# Connectors.net
KiCad netlist of a schematic drawn in Altium Designer
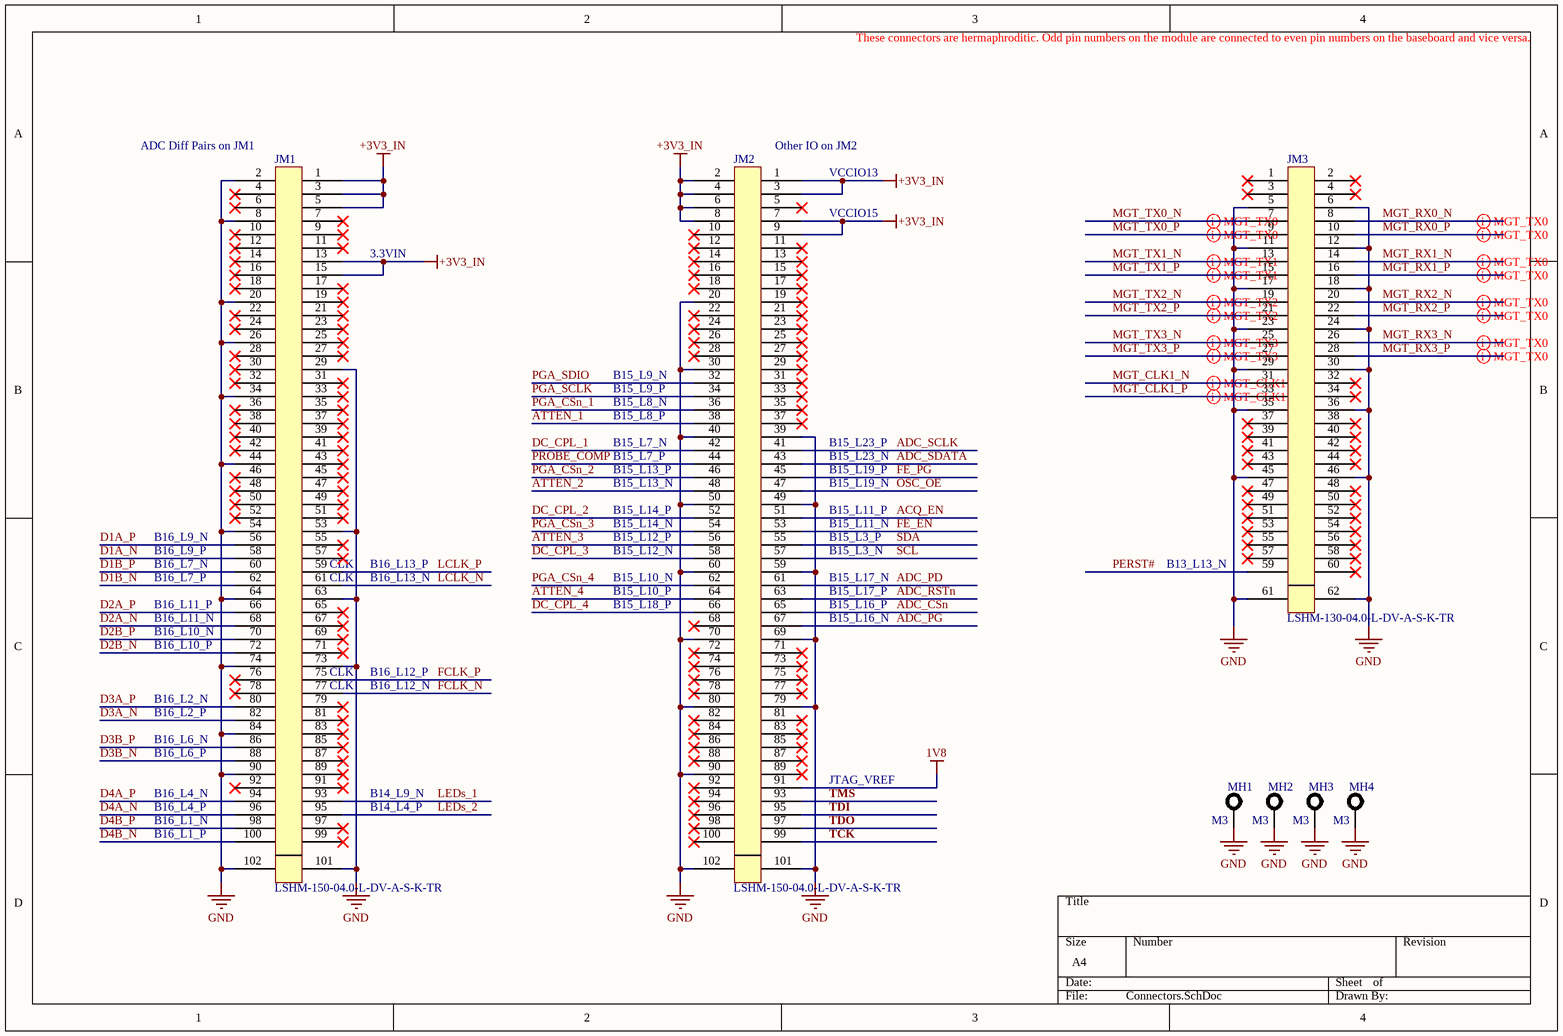
[diagram p0: Connectors.SchDoc]

(export (version "E")
  (design (tool "Eeschema 10.0.6"))
  (components
    (comp (ref "JM1")
      (value "LSHM-150-04.0-L-DV-A-S-K-TR")
      (footprint "SAM_LSHM-150-XX.X-XX-DV-A-S")
      (libsource (lib "DSO") (part "CONN LSHM-150-04.0-L-DV-A-S-K-TR"))
    )
    (comp (ref "JM2")
      (value "LSHM-150-04.0-L-DV-A-S-K-TR")
      (footprint "SAM_LSHM-150-XX.X-XX-DV-A-S")
      (libsource (lib "DSO") (part "CONN LSHM-150-04.0-L-DV-A-S-K-TR"))
    )
    (comp (ref "JM3")
      (value "LSHM-130-04.0-L-DV-A-S-K-TR")
      (footprint "SAM_LSHM-130-XX.X-XX-DV-A-S")
      (libsource (lib "DSO") (part "CONN LSHM-130-04.0-L-DV-A-S-K-TR"))
    )
    (comp (ref "MH1") (value "M3") (footprint "MH M3") (libsource (lib "DSO") (part "MH M3")))
    (comp (ref "MH2") (value "M3") (footprint "MH M3") (libsource (lib "DSO") (part "MH M3")))
    (comp (ref "MH3") (value "M3") (footprint "MH M3") (libsource (lib "DSO") (part "MH M3")))
    (comp (ref "MH4") (value "M3") (footprint "MH M3") (libsource (lib "DSO") (part "MH M3")))
  )
  (nets
    (net (code "1") (name "+3V3_IN") (class "Default")
      (node (ref "JM1") (pin "1") (pinfunction "1_1") (pintype "passive"))
      (node (ref "JM1") (pin "13") (pinfunction "13_13") (pintype "passive"))
      (node (ref "JM1") (pin "15") (pinfunction "15_15") (pintype "passive"))
      (node (ref "JM1") (pin "3") (pinfunction "3_3") (pintype "passive"))
      (node (ref "JM1") (pin "5") (pinfunction "5_5") (pintype "passive"))
      (node (ref "JM2") (pin "1") (pinfunction "1_1") (pintype "passive"))
      (node (ref "JM2") (pin "2") (pinfunction "2_2") (pintype "passive"))
      (node (ref "JM2") (pin "3") (pinfunction "3_3") (pintype "passive"))
      (node (ref "JM2") (pin "4") (pinfunction "4_4") (pintype "passive"))
      (node (ref "JM2") (pin "6") (pinfunction "6_6") (pintype "passive"))
      (node (ref "JM2") (pin "7") (pinfunction "7_7") (pintype "passive"))
      (node (ref "JM2") (pin "8") (pinfunction "8_8") (pintype "passive"))
      (node (ref "JM2") (pin "9") (pinfunction "9_9") (pintype "passive"))
    )
    (net (code "2") (name "/ACQ_EN") (class "Default")
      (node (ref "JM2") (pin "51") (pinfunction "51_51") (pintype "passive"))
    )
    (net (code "3") (name "/ADC_CSn") (class "Default")
      (node (ref "JM2") (pin "65") (pinfunction "65_65") (pintype "passive"))
    )
    (net (code "4") (name "/ADC_PD") (class "Default")
      (node (ref "JM2") (pin "61") (pinfunction "61_61") (pintype "passive"))
    )
    (net (code "5") (name "/ADC_PG") (class "Default")
      (node (ref "JM2") (pin "67") (pinfunction "67_67") (pintype "passive"))
    )
    (net (code "6") (name "/ADC_RSTn") (class "Default")
      (node (ref "JM2") (pin "63") (pinfunction "63_63") (pintype "passive"))
    )
    (net (code "7") (name "/ADC_SCLK") (class "Default")
      (node (ref "JM2") (pin "41") (pinfunction "41_41") (pintype "passive"))
    )
    (net (code "8") (name "/ADC_SDATA") (class "Default")
      (node (ref "JM2") (pin "43") (pinfunction "43_43") (pintype "passive"))
    )
    (net (code "9") (name "/ATTEN_1") (class "Default")
      (node (ref "JM2") (pin "38") (pinfunction "38_38") (pintype "passive"))
    )
    (net (code "10") (name "/ATTEN_2") (class "Default")
      (node (ref "JM2") (pin "48") (pinfunction "48_48") (pintype "passive"))
    )
    (net (code "11") (name "/ATTEN_3") (class "Default")
      (node (ref "JM2") (pin "56") (pinfunction "56_56") (pintype "passive"))
    )
    (net (code "12") (name "/ATTEN_4") (class "Default")
      (node (ref "JM2") (pin "64") (pinfunction "64_64") (pintype "passive"))
    )
    (net (code "13") (name "/D1A_N") (class "Default")
      (node (ref "JM1") (pin "58") (pinfunction "58_58") (pintype "passive"))
    )
    (net (code "14") (name "/D1A_P") (class "Default")
      (node (ref "JM1") (pin "56") (pinfunction "56_56") (pintype "passive"))
    )
    (net (code "15") (name "/D1B_N") (class "Default")
      (node (ref "JM1") (pin "62") (pinfunction "62_62") (pintype "passive"))
    )
    (net (code "16") (name "/D1B_P") (class "Default")
      (node (ref "JM1") (pin "60") (pinfunction "60_60") (pintype "passive"))
    )
    (net (code "17") (name "/D2A_N") (class "Default")
      (node (ref "JM1") (pin "68") (pinfunction "68_68") (pintype "passive"))
    )
    (net (code "18") (name "/D2A_P") (class "Default")
      (node (ref "JM1") (pin "66") (pinfunction "66_66") (pintype "passive"))
    )
    (net (code "19") (name "/D2B_N") (class "Default")
      (node (ref "JM1") (pin "72") (pinfunction "72_72") (pintype "passive"))
    )
    (net (code "20") (name "/D2B_P") (class "Default")
      (node (ref "JM1") (pin "70") (pinfunction "70_70") (pintype "passive"))
    )
    (net (code "21") (name "/D3A_N") (class "Default")
      (node (ref "JM1") (pin "82") (pinfunction "82_82") (pintype "passive"))
    )
    (net (code "22") (name "/D3A_P") (class "Default")
      (node (ref "JM1") (pin "80") (pinfunction "80_80") (pintype "passive"))
    )
    (net (code "23") (name "/D3B_N") (class "Default")
      (node (ref "JM1") (pin "88") (pinfunction "88_88") (pintype "passive"))
    )
    (net (code "24") (name "/D3B_P") (class "Default")
      (node (ref "JM1") (pin "86") (pinfunction "86_86") (pintype "passive"))
    )
    (net (code "25") (name "/D4A_N") (class "Default")
      (node (ref "JM1") (pin "96") (pinfunction "96_96") (pintype "passive"))
    )
    (net (code "26") (name "/D4A_P") (class "Default")
      (node (ref "JM1") (pin "94") (pinfunction "94_94") (pintype "passive"))
    )
    (net (code "27") (name "/D4B_N") (class "Default")
      (node (ref "JM1") (pin "100") (pinfunction "100_100") (pintype "passive"))
    )
    (net (code "28") (name "/D4B_P") (class "Default")
      (node (ref "JM1") (pin "98") (pinfunction "98_98") (pintype "passive"))
    )
    (net (code "29") (name "/DC_CPL_1") (class "Default")
      (node (ref "JM2") (pin "42") (pinfunction "42_42") (pintype "passive"))
    )
    (net (code "30") (name "/DC_CPL_2") (class "Default")
      (node (ref "JM2") (pin "52") (pinfunction "52_52") (pintype "passive"))
    )
    (net (code "31") (name "/DC_CPL_3") (class "Default")
      (node (ref "JM2") (pin "58") (pinfunction "58_58") (pintype "passive"))
    )
    (net (code "32") (name "/DC_CPL_4") (class "Default")
      (node (ref "JM2") (pin "66") (pinfunction "66_66") (pintype "passive"))
    )
    (net (code "33") (name "/FCLK_N") (class "Default")
      (node (ref "JM1") (pin "77") (pinfunction "77_77") (pintype "passive"))
    )
    (net (code "34") (name "/FCLK_P") (class "Default")
      (node (ref "JM1") (pin "75") (pinfunction "75_75") (pintype "passive"))
    )
    (net (code "35") (name "/FE_EN") (class "Default")
      (node (ref "JM2") (pin "53") (pinfunction "53_53") (pintype "passive"))
    )
    (net (code "36") (name "/FE_PG") (class "Default")
      (node (ref "JM2") (pin "45") (pinfunction "45_45") (pintype "passive"))
    )
    (net (code "37") (name "/LCLK_N") (class "Default")
      (node (ref "JM1") (pin "61") (pinfunction "61_61") (pintype "passive"))
    )
    (net (code "38") (name "/LCLK_P") (class "Default")
      (node (ref "JM1") (pin "59") (pinfunction "59_59") (pintype "passive"))
    )
    (net (code "39") (name "/LEDs_1") (class "Default")
      (node (ref "JM1") (pin "93") (pinfunction "93_93") (pintype "passive"))
    )
    (net (code "40") (name "/LEDs_2") (class "Default")
      (node (ref "JM1") (pin "95") (pinfunction "95_95") (pintype "passive"))
    )
    (net (code "41") (name "/MGT_CLK1_N") (class "Default")
      (node (ref "JM3") (pin "31") (pinfunction "31_31") (pintype "passive"))
    )
    (net (code "42") (name "/MGT_CLK1_P") (class "Default")
      (node (ref "JM3") (pin "33") (pinfunction "33_33") (pintype "passive"))
    )
    (net (code "43") (name "/MGT_RX0_N") (class "Default")
      (node (ref "JM3") (pin "8") (pinfunction "8_8") (pintype "passive"))
    )
    (net (code "44") (name "/MGT_RX0_P") (class "Default")
      (node (ref "JM3") (pin "10") (pinfunction "10_10") (pintype "passive"))
    )
    (net (code "45") (name "/MGT_RX1_N") (class "Default")
      (node (ref "JM3") (pin "14") (pinfunction "14_14") (pintype "passive"))
    )
    (net (code "46") (name "/MGT_RX1_P") (class "Default")
      (node (ref "JM3") (pin "16") (pinfunction "16_16") (pintype "passive"))
    )
    (net (code "47") (name "/MGT_RX2_N") (class "Default")
      (node (ref "JM3") (pin "20") (pinfunction "20_20") (pintype "passive"))
    )
    (net (code "48") (name "/MGT_RX2_P") (class "Default")
      (node (ref "JM3") (pin "22") (pinfunction "22_22") (pintype "passive"))
    )
    (net (code "49") (name "/MGT_RX3_N") (class "Default")
      (node (ref "JM3") (pin "26") (pinfunction "26_26") (pintype "passive"))
    )
    (net (code "50") (name "/MGT_RX3_P") (class "Default")
      (node (ref "JM3") (pin "28") (pinfunction "28_28") (pintype "passive"))
    )
    (net (code "51") (name "/MGT_TX0_N") (class "Default")
      (node (ref "JM3") (pin "7") (pinfunction "7_7") (pintype "passive"))
    )
    (net (code "52") (name "/MGT_TX0_P") (class "Default")
      (node (ref "JM3") (pin "9") (pinfunction "9_9") (pintype "passive"))
    )
    (net (code "53") (name "/MGT_TX1_N") (class "Default")
      (node (ref "JM3") (pin "13") (pinfunction "13_13") (pintype "passive"))
    )
    (net (code "54") (name "/MGT_TX1_P") (class "Default")
      (node (ref "JM3") (pin "15") (pinfunction "15_15") (pintype "passive"))
    )
    (net (code "55") (name "/MGT_TX2_N") (class "Default")
      (node (ref "JM3") (pin "19") (pinfunction "19_19") (pintype "passive"))
    )
    (net (code "56") (name "/MGT_TX2_P") (class "Default")
      (node (ref "JM3") (pin "21") (pinfunction "21_21") (pintype "passive"))
    )
    (net (code "57") (name "/MGT_TX3_N") (class "Default")
      (node (ref "JM3") (pin "25") (pinfunction "25_25") (pintype "passive"))
    )
    (net (code "58") (name "/MGT_TX3_P") (class "Default")
      (node (ref "JM3") (pin "27") (pinfunction "27_27") (pintype "passive"))
    )
    (net (code "59") (name "/OSC_OE") (class "Default")
      (node (ref "JM2") (pin "47") (pinfunction "47_47") (pintype "passive"))
    )
    (net (code "60") (name "/PERST#") (class "Default")
      (node (ref "JM3") (pin "59") (pinfunction "59_59") (pintype "passive"))
    )
    (net (code "61") (name "/PGA_CSn_1") (class "Default")
      (node (ref "JM2") (pin "36") (pinfunction "36_36") (pintype "passive"))
    )
    (net (code "62") (name "/PGA_CSn_2") (class "Default")
      (node (ref "JM2") (pin "46") (pinfunction "46_46") (pintype "passive"))
    )
    (net (code "63") (name "/PGA_CSn_3") (class "Default")
      (node (ref "JM2") (pin "54") (pinfunction "54_54") (pintype "passive"))
    )
    (net (code "64") (name "/PGA_CSn_4") (class "Default")
      (node (ref "JM2") (pin "62") (pinfunction "62_62") (pintype "passive"))
    )
    (net (code "65") (name "/PGA_SCLK") (class "Default")
      (node (ref "JM2") (pin "34") (pinfunction "34_34") (pintype "passive"))
    )
    (net (code "66") (name "/PGA_SDIO") (class "Default")
      (node (ref "JM2") (pin "32") (pinfunction "32_32") (pintype "passive"))
    )
    (net (code "67") (name "/PROBE_COMP") (class "Default")
      (node (ref "JM2") (pin "44") (pinfunction "44_44") (pintype "passive"))
    )
    (net (code "68") (name "/SCL") (class "Default")
      (node (ref "JM2") (pin "57") (pinfunction "57_57") (pintype "passive"))
    )
    (net (code "69") (name "/SDA") (class "Default")
      (node (ref "JM2") (pin "55") (pinfunction "55_55") (pintype "passive"))
    )
    (net (code "70") (name "/TCK") (class "Default")
      (node (ref "JM2") (pin "99") (pinfunction "99_99") (pintype "passive"))
    )
    (net (code "71") (name "/TDI") (class "Default")
      (node (ref "JM2") (pin "95") (pinfunction "95_95") (pintype "passive"))
    )
    (net (code "72") (name "/TDO") (class "Default")
      (node (ref "JM2") (pin "97") (pinfunction "97_97") (pintype "passive"))
    )
    (net (code "73") (name "/TMS") (class "Default")
      (node (ref "JM2") (pin "93") (pinfunction "93_93") (pintype "passive"))
    )
    (net (code "74") (name "1V8") (class "Default")
      (node (ref "JM2") (pin "91") (pinfunction "91_91") (pintype "passive"))
    )
    (net (code "75") (name "GND") (class "Default")
      (node (ref "JM1") (pin "101") (pinfunction "101_101") (pintype "passive"))
      (node (ref "JM1") (pin "102") (pinfunction "102_102") (pintype "passive"))
      (node (ref "JM1") (pin "2") (pinfunction "2_2") (pintype "passive"))
      (node (ref "JM1") (pin "20") (pinfunction "20_20") (pintype "passive"))
      (node (ref "JM1") (pin "26") (pinfunction "26_26") (pintype "passive"))
      (node (ref "JM1") (pin "29") (pinfunction "29_29") (pintype "passive"))
      (node (ref "JM1") (pin "34") (pinfunction "34_34") (pintype "passive"))
      (node (ref "JM1") (pin "44") (pinfunction "44_44") (pintype "passive"))
      (node (ref "JM1") (pin "53") (pinfunction "53_53") (pintype "passive"))
      (node (ref "JM1") (pin "54") (pinfunction "54_54") (pintype "passive"))
      (node (ref "JM1") (pin "63") (pinfunction "63_63") (pintype "passive"))
      (node (ref "JM1") (pin "64") (pinfunction "64_64") (pintype "passive"))
      (node (ref "JM1") (pin "73") (pinfunction "73_73") (pintype "passive"))
      (node (ref "JM1") (pin "74") (pinfunction "74_74") (pintype "passive"))
      (node (ref "JM1") (pin "8") (pinfunction "8_8") (pintype "passive"))
      (node (ref "JM1") (pin "84") (pinfunction "84_84") (pintype "passive"))
      (node (ref "JM1") (pin "90") (pinfunction "90_90") (pintype "passive"))
      (node (ref "JM2") (pin "101") (pinfunction "101_101") (pintype "passive"))
      (node (ref "JM2") (pin "102") (pinfunction "102_102") (pintype "passive"))
      (node (ref "JM2") (pin "20") (pinfunction "20_20") (pintype "passive"))
      (node (ref "JM2") (pin "30") (pinfunction "30_30") (pintype "passive"))
      (node (ref "JM2") (pin "39") (pinfunction "39_39") (pintype "passive"))
      (node (ref "JM2") (pin "40") (pinfunction "40_40") (pintype "passive"))
      (node (ref "JM2") (pin "49") (pinfunction "49_49") (pintype "passive"))
      (node (ref "JM2") (pin "50") (pinfunction "50_50") (pintype "passive"))
      (node (ref "JM2") (pin "59") (pinfunction "59_59") (pintype "passive"))
      (node (ref "JM2") (pin "60") (pinfunction "60_60") (pintype "passive"))
      (node (ref "JM2") (pin "69") (pinfunction "69_69") (pintype "passive"))
      (node (ref "JM2") (pin "70") (pinfunction "70_70") (pintype "passive"))
      (node (ref "JM2") (pin "79") (pinfunction "79_79") (pintype "passive"))
      (node (ref "JM2") (pin "80") (pinfunction "80_80") (pintype "passive"))
      (node (ref "JM2") (pin "90") (pinfunction "90_90") (pintype "passive"))
      (node (ref "JM3") (pin "11") (pinfunction "11_11") (pintype "passive"))
      (node (ref "JM3") (pin "12") (pinfunction "12_12") (pintype "passive"))
      (node (ref "JM3") (pin "17") (pinfunction "17_17") (pintype "passive"))
      (node (ref "JM3") (pin "18") (pinfunction "18_18") (pintype "passive"))
      (node (ref "JM3") (pin "23") (pinfunction "23_23") (pintype "passive"))
      (node (ref "JM3") (pin "24") (pinfunction "24_24") (pintype "passive"))
      (node (ref "JM3") (pin "29") (pinfunction "29_29") (pintype "passive"))
      (node (ref "JM3") (pin "30") (pinfunction "30_30") (pintype "passive"))
      (node (ref "JM3") (pin "35") (pinfunction "35_35") (pintype "passive"))
      (node (ref "JM3") (pin "36") (pinfunction "36_36") (pintype "passive"))
      (node (ref "JM3") (pin "45") (pinfunction "45_45") (pintype "passive"))
      (node (ref "JM3") (pin "46") (pinfunction "46_46") (pintype "passive"))
      (node (ref "JM3") (pin "5") (pinfunction "5_5") (pintype "passive"))
      (node (ref "JM3") (pin "6") (pinfunction "6_6") (pintype "passive"))
      (node (ref "JM3") (pin "61") (pinfunction "61_61") (pintype "passive"))
      (node (ref "JM3") (pin "62") (pinfunction "62_62") (pintype "passive"))
      (node (ref "MH1") (pin "1") (pinfunction "1_1") (pintype "passive"))
      (node (ref "MH2") (pin "1") (pinfunction "1_1") (pintype "passive"))
      (node (ref "MH3") (pin "1") (pinfunction "1_1") (pintype "passive"))
      (node (ref "MH4") (pin "1") (pinfunction "1_1") (pintype "passive"))
    )
    (net (code "76") (name "unconnected-(JM1-Pad4)") (class "Default")
      (node (ref "JM1") (pin "4") (pinfunction "4_4") (pintype "passive+no_connect"))
    )
    (net (code "77") (name "unconnected-(JM1-Pad6)") (class "Default")
      (node (ref "JM1") (pin "6") (pinfunction "6_6") (pintype "passive+no_connect"))
    )
    (net (code "78") (name "unconnected-(JM1-Pad7)") (class "Default")
      (node (ref "JM1") (pin "7") (pinfunction "7_7") (pintype "passive+no_connect"))
    )
    (net (code "79") (name "unconnected-(JM1-Pad9)") (class "Default")
      (node (ref "JM1") (pin "9") (pinfunction "9_9") (pintype "passive+no_connect"))
    )
    (net (code "80") (name "unconnected-(JM1-Pad10)") (class "Default")
      (node (ref "JM1") (pin "10") (pinfunction "10_10") (pintype "passive+no_connect"))
    )
    (net (code "81") (name "unconnected-(JM1-Pad11)") (class "Default")
      (node (ref "JM1") (pin "11") (pinfunction "11_11") (pintype "passive+no_connect"))
    )
    (net (code "82") (name "unconnected-(JM1-Pad12)") (class "Default")
      (node (ref "JM1") (pin "12") (pinfunction "12_12") (pintype "passive+no_connect"))
    )
    (net (code "83") (name "unconnected-(JM1-Pad14)") (class "Default")
      (node (ref "JM1") (pin "14") (pinfunction "14_14") (pintype "passive+no_connect"))
    )
    (net (code "84") (name "unconnected-(JM1-Pad16)") (class "Default")
      (node (ref "JM1") (pin "16") (pinfunction "16_16") (pintype "passive+no_connect"))
    )
    (net (code "85") (name "unconnected-(JM1-Pad17)") (class "Default")
      (node (ref "JM1") (pin "17") (pinfunction "17_17") (pintype "passive+no_connect"))
    )
    (net (code "86") (name "unconnected-(JM1-Pad18)") (class "Default")
      (node (ref "JM1") (pin "18") (pinfunction "18_18") (pintype "passive+no_connect"))
    )
    (net (code "87") (name "unconnected-(JM1-Pad19)") (class "Default")
      (node (ref "JM1") (pin "19") (pinfunction "19_19") (pintype "passive+no_connect"))
    )
    (net (code "88") (name "unconnected-(JM1-Pad21)") (class "Default")
      (node (ref "JM1") (pin "21") (pinfunction "21_21") (pintype "passive+no_connect"))
    )
    (net (code "89") (name "unconnected-(JM1-Pad22)") (class "Default")
      (node (ref "JM1") (pin "22") (pinfunction "22_22") (pintype "passive+no_connect"))
    )
    (net (code "90") (name "unconnected-(JM1-Pad23)") (class "Default")
      (node (ref "JM1") (pin "23") (pinfunction "23_23") (pintype "passive+no_connect"))
    )
    (net (code "91") (name "unconnected-(JM1-Pad24)") (class "Default")
      (node (ref "JM1") (pin "24") (pinfunction "24_24") (pintype "passive+no_connect"))
    )
    (net (code "92") (name "unconnected-(JM1-Pad25)") (class "Default")
      (node (ref "JM1") (pin "25") (pinfunction "25_25") (pintype "passive+no_connect"))
    )
    (net (code "93") (name "unconnected-(JM1-Pad27)") (class "Default")
      (node (ref "JM1") (pin "27") (pinfunction "27_27") (pintype "passive+no_connect"))
    )
    (net (code "94") (name "unconnected-(JM1-Pad28)") (class "Default")
      (node (ref "JM1") (pin "28") (pinfunction "28_28") (pintype "passive+no_connect"))
    )
    (net (code "95") (name "unconnected-(JM1-Pad30)") (class "Default")
      (node (ref "JM1") (pin "30") (pinfunction "30_30") (pintype "passive+no_connect"))
    )
    (net (code "96") (name "unconnected-(JM1-Pad31)") (class "Default")
      (node (ref "JM1") (pin "31") (pinfunction "31_31") (pintype "passive+no_connect"))
    )
    (net (code "97") (name "unconnected-(JM1-Pad32)") (class "Default")
      (node (ref "JM1") (pin "32") (pinfunction "32_32") (pintype "passive+no_connect"))
    )
    (net (code "98") (name "unconnected-(JM1-Pad33)") (class "Default")
      (node (ref "JM1") (pin "33") (pinfunction "33_33") (pintype "passive+no_connect"))
    )
    (net (code "99") (name "unconnected-(JM1-Pad35)") (class "Default")
      (node (ref "JM1") (pin "35") (pinfunction "35_35") (pintype "passive+no_connect"))
    )
    (net (code "100") (name "unconnected-(JM1-Pad36)") (class "Default")
      (node (ref "JM1") (pin "36") (pinfunction "36_36") (pintype "passive+no_connect"))
    )
    (net (code "101") (name "unconnected-(JM1-Pad37)") (class "Default")
      (node (ref "JM1") (pin "37") (pinfunction "37_37") (pintype "passive+no_connect"))
    )
    (net (code "102") (name "unconnected-(JM1-Pad38)") (class "Default")
      (node (ref "JM1") (pin "38") (pinfunction "38_38") (pintype "passive+no_connect"))
    )
    (net (code "103") (name "unconnected-(JM1-Pad39)") (class "Default")
      (node (ref "JM1") (pin "39") (pinfunction "39_39") (pintype "passive+no_connect"))
    )
    (net (code "104") (name "unconnected-(JM1-Pad40)") (class "Default")
      (node (ref "JM1") (pin "40") (pinfunction "40_40") (pintype "passive+no_connect"))
    )
    (net (code "105") (name "unconnected-(JM1-Pad41)") (class "Default")
      (node (ref "JM1") (pin "41") (pinfunction "41_41") (pintype "passive+no_connect"))
    )
    (net (code "106") (name "unconnected-(JM1-Pad42)") (class "Default")
      (node (ref "JM1") (pin "42") (pinfunction "42_42") (pintype "passive+no_connect"))
    )
    (net (code "107") (name "unconnected-(JM1-Pad43)") (class "Default")
      (node (ref "JM1") (pin "43") (pinfunction "43_43") (pintype "passive+no_connect"))
    )
    (net (code "108") (name "unconnected-(JM1-Pad45)") (class "Default")
      (node (ref "JM1") (pin "45") (pinfunction "45_45") (pintype "passive+no_connect"))
    )
    (net (code "109") (name "unconnected-(JM1-Pad46)") (class "Default")
      (node (ref "JM1") (pin "46") (pinfunction "46_46") (pintype "passive+no_connect"))
    )
    (net (code "110") (name "unconnected-(JM1-Pad47)") (class "Default")
      (node (ref "JM1") (pin "47") (pinfunction "47_47") (pintype "passive+no_connect"))
    )
    (net (code "111") (name "unconnected-(JM1-Pad48)") (class "Default")
      (node (ref "JM1") (pin "48") (pinfunction "48_48") (pintype "passive+no_connect"))
    )
    (net (code "112") (name "unconnected-(JM1-Pad49)") (class "Default")
      (node (ref "JM1") (pin "49") (pinfunction "49_49") (pintype "passive+no_connect"))
    )
    (net (code "113") (name "unconnected-(JM1-Pad50)") (class "Default")
      (node (ref "JM1") (pin "50") (pinfunction "50_50") (pintype "passive+no_connect"))
    )
    (net (code "114") (name "unconnected-(JM1-Pad51)") (class "Default")
      (node (ref "JM1") (pin "51") (pinfunction "51_51") (pintype "passive+no_connect"))
    )
    (net (code "115") (name "unconnected-(JM1-Pad52)") (class "Default")
      (node (ref "JM1") (pin "52") (pinfunction "52_52") (pintype "passive+no_connect"))
    )
    (net (code "116") (name "unconnected-(JM1-Pad55)") (class "Default")
      (node (ref "JM1") (pin "55") (pinfunction "55_55") (pintype "passive+no_connect"))
    )
    (net (code "117") (name "unconnected-(JM1-Pad57)") (class "Default")
      (node (ref "JM1") (pin "57") (pinfunction "57_57") (pintype "passive+no_connect"))
    )
    (net (code "118") (name "unconnected-(JM1-Pad65)") (class "Default")
      (node (ref "JM1") (pin "65") (pinfunction "65_65") (pintype "passive+no_connect"))
    )
    (net (code "119") (name "unconnected-(JM1-Pad67)") (class "Default")
      (node (ref "JM1") (pin "67") (pinfunction "67_67") (pintype "passive+no_connect"))
    )
    (net (code "120") (name "unconnected-(JM1-Pad69)") (class "Default")
      (node (ref "JM1") (pin "69") (pinfunction "69_69") (pintype "passive+no_connect"))
    )
    (net (code "121") (name "unconnected-(JM1-Pad71)") (class "Default")
      (node (ref "JM1") (pin "71") (pinfunction "71_71") (pintype "passive+no_connect"))
    )
    (net (code "122") (name "unconnected-(JM1-Pad76)") (class "Default")
      (node (ref "JM1") (pin "76") (pinfunction "76_76") (pintype "passive+no_connect"))
    )
    (net (code "123") (name "unconnected-(JM1-Pad78)") (class "Default")
      (node (ref "JM1") (pin "78") (pinfunction "78_78") (pintype "passive+no_connect"))
    )
    (net (code "124") (name "unconnected-(JM1-Pad79)") (class "Default")
      (node (ref "JM1") (pin "79") (pinfunction "79_79") (pintype "passive+no_connect"))
    )
    (net (code "125") (name "unconnected-(JM1-Pad81)") (class "Default")
      (node (ref "JM1") (pin "81") (pinfunction "81_81") (pintype "passive+no_connect"))
    )
    (net (code "126") (name "unconnected-(JM1-Pad83)") (class "Default")
      (node (ref "JM1") (pin "83") (pinfunction "83_83") (pintype "passive+no_connect"))
    )
    (net (code "127") (name "unconnected-(JM1-Pad85)") (class "Default")
      (node (ref "JM1") (pin "85") (pinfunction "85_85") (pintype "passive+no_connect"))
    )
    (net (code "128") (name "unconnected-(JM1-Pad87)") (class "Default")
      (node (ref "JM1") (pin "87") (pinfunction "87_87") (pintype "passive+no_connect"))
    )
    (net (code "129") (name "unconnected-(JM1-Pad89)") (class "Default")
      (node (ref "JM1") (pin "89") (pinfunction "89_89") (pintype "passive+no_connect"))
    )
    (net (code "130") (name "unconnected-(JM1-Pad91)") (class "Default")
      (node (ref "JM1") (pin "91") (pinfunction "91_91") (pintype "passive+no_connect"))
    )
    (net (code "131") (name "unconnected-(JM1-Pad92)") (class "Default")
      (node (ref "JM1") (pin "92") (pinfunction "92_92") (pintype "passive+no_connect"))
    )
    (net (code "132") (name "unconnected-(JM1-Pad97)") (class "Default")
      (node (ref "JM1") (pin "97") (pinfunction "97_97") (pintype "passive+no_connect"))
    )
    (net (code "133") (name "unconnected-(JM1-Pad99)") (class "Default")
      (node (ref "JM1") (pin "99") (pinfunction "99_99") (pintype "passive+no_connect"))
    )
    (net (code "134") (name "unconnected-(JM2-Pad5)") (class "Default")
      (node (ref "JM2") (pin "5") (pinfunction "5_5") (pintype "passive+no_connect"))
    )
    (net (code "135") (name "unconnected-(JM2-Pad10)") (class "Default")
      (node (ref "JM2") (pin "10") (pinfunction "10_10") (pintype "passive+no_connect"))
    )
    (net (code "136") (name "unconnected-(JM2-Pad11)") (class "Default")
      (node (ref "JM2") (pin "11") (pinfunction "11_11") (pintype "passive+no_connect"))
    )
    (net (code "137") (name "unconnected-(JM2-Pad12)") (class "Default")
      (node (ref "JM2") (pin "12") (pinfunction "12_12") (pintype "passive+no_connect"))
    )
    (net (code "138") (name "unconnected-(JM2-Pad13)") (class "Default")
      (node (ref "JM2") (pin "13") (pinfunction "13_13") (pintype "passive+no_connect"))
    )
    (net (code "139") (name "unconnected-(JM2-Pad14)") (class "Default")
      (node (ref "JM2") (pin "14") (pinfunction "14_14") (pintype "passive+no_connect"))
    )
    (net (code "140") (name "unconnected-(JM2-Pad15)") (class "Default")
      (node (ref "JM2") (pin "15") (pinfunction "15_15") (pintype "passive+no_connect"))
    )
    (net (code "141") (name "unconnected-(JM2-Pad16)") (class "Default")
      (node (ref "JM2") (pin "16") (pinfunction "16_16") (pintype "passive+no_connect"))
    )
    (net (code "142") (name "unconnected-(JM2-Pad17)") (class "Default")
      (node (ref "JM2") (pin "17") (pinfunction "17_17") (pintype "passive+no_connect"))
    )
    (net (code "143") (name "unconnected-(JM2-Pad18)") (class "Default")
      (node (ref "JM2") (pin "18") (pinfunction "18_18") (pintype "passive+no_connect"))
    )
    (net (code "144") (name "unconnected-(JM2-Pad19)") (class "Default")
      (node (ref "JM2") (pin "19") (pinfunction "19_19") (pintype "passive+no_connect"))
    )
    (net (code "145") (name "unconnected-(JM2-Pad21)") (class "Default")
      (node (ref "JM2") (pin "21") (pinfunction "21_21") (pintype "passive+no_connect"))
    )
    (net (code "146") (name "unconnected-(JM2-Pad22)") (class "Default")
      (node (ref "JM2") (pin "22") (pinfunction "22_22") (pintype "passive+no_connect"))
    )
    (net (code "147") (name "unconnected-(JM2-Pad23)") (class "Default")
      (node (ref "JM2") (pin "23") (pinfunction "23_23") (pintype "passive+no_connect"))
    )
    (net (code "148") (name "unconnected-(JM2-Pad24)") (class "Default")
      (node (ref "JM2") (pin "24") (pinfunction "24_24") (pintype "passive+no_connect"))
    )
    (net (code "149") (name "unconnected-(JM2-Pad25)") (class "Default")
      (node (ref "JM2") (pin "25") (pinfunction "25_25") (pintype "passive+no_connect"))
    )
    (net (code "150") (name "unconnected-(JM2-Pad26)") (class "Default")
      (node (ref "JM2") (pin "26") (pinfunction "26_26") (pintype "passive+no_connect"))
    )
    (net (code "151") (name "unconnected-(JM2-Pad27)") (class "Default")
      (node (ref "JM2") (pin "27") (pinfunction "27_27") (pintype "passive+no_connect"))
    )
    (net (code "152") (name "unconnected-(JM2-Pad28)") (class "Default")
      (node (ref "JM2") (pin "28") (pinfunction "28_28") (pintype "passive+no_connect"))
    )
    (net (code "153") (name "unconnected-(JM2-Pad29)") (class "Default")
      (node (ref "JM2") (pin "29") (pinfunction "29_29") (pintype "passive+no_connect"))
    )
    (net (code "154") (name "unconnected-(JM2-Pad31)") (class "Default")
      (node (ref "JM2") (pin "31") (pinfunction "31_31") (pintype "passive+no_connect"))
    )
    (net (code "155") (name "unconnected-(JM2-Pad33)") (class "Default")
      (node (ref "JM2") (pin "33") (pinfunction "33_33") (pintype "passive+no_connect"))
    )
    (net (code "156") (name "unconnected-(JM2-Pad35)") (class "Default")
      (node (ref "JM2") (pin "35") (pinfunction "35_35") (pintype "passive+no_connect"))
    )
    (net (code "157") (name "unconnected-(JM2-Pad37)") (class "Default")
      (node (ref "JM2") (pin "37") (pinfunction "37_37") (pintype "passive+no_connect"))
    )
    (net (code "158") (name "unconnected-(JM2-Pad68)") (class "Default")
      (node (ref "JM2") (pin "68") (pinfunction "68_68") (pintype "passive+no_connect"))
    )
    (net (code "159") (name "unconnected-(JM2-Pad71)") (class "Default")
      (node (ref "JM2") (pin "71") (pinfunction "71_71") (pintype "passive+no_connect"))
    )
    (net (code "160") (name "unconnected-(JM2-Pad72)") (class "Default")
      (node (ref "JM2") (pin "72") (pinfunction "72_72") (pintype "passive+no_connect"))
    )
    (net (code "161") (name "unconnected-(JM2-Pad73)") (class "Default")
      (node (ref "JM2") (pin "73") (pinfunction "73_73") (pintype "passive+no_connect"))
    )
    (net (code "162") (name "unconnected-(JM2-Pad74)") (class "Default")
      (node (ref "JM2") (pin "74") (pinfunction "74_74") (pintype "passive+no_connect"))
    )
    (net (code "163") (name "unconnected-(JM2-Pad75)") (class "Default")
      (node (ref "JM2") (pin "75") (pinfunction "75_75") (pintype "passive+no_connect"))
    )
    (net (code "164") (name "unconnected-(JM2-Pad76)") (class "Default")
      (node (ref "JM2") (pin "76") (pinfunction "76_76") (pintype "passive+no_connect"))
    )
    (net (code "165") (name "unconnected-(JM2-Pad77)") (class "Default")
      (node (ref "JM2") (pin "77") (pinfunction "77_77") (pintype "passive+no_connect"))
    )
    (net (code "166") (name "unconnected-(JM2-Pad78)") (class "Default")
      (node (ref "JM2") (pin "78") (pinfunction "78_78") (pintype "passive+no_connect"))
    )
    (net (code "167") (name "unconnected-(JM2-Pad81)") (class "Default")
      (node (ref "JM2") (pin "81") (pinfunction "81_81") (pintype "passive+no_connect"))
    )
    (net (code "168") (name "unconnected-(JM2-Pad82)") (class "Default")
      (node (ref "JM2") (pin "82") (pinfunction "82_82") (pintype "passive+no_connect"))
    )
    (net (code "169") (name "unconnected-(JM2-Pad83)") (class "Default")
      (node (ref "JM2") (pin "83") (pinfunction "83_83") (pintype "passive+no_connect"))
    )
    (net (code "170") (name "unconnected-(JM2-Pad84)") (class "Default")
      (node (ref "JM2") (pin "84") (pinfunction "84_84") (pintype "passive+no_connect"))
    )
    (net (code "171") (name "unconnected-(JM2-Pad85)") (class "Default")
      (node (ref "JM2") (pin "85") (pinfunction "85_85") (pintype "passive+no_connect"))
    )
    (net (code "172") (name "unconnected-(JM2-Pad86)") (class "Default")
      (node (ref "JM2") (pin "86") (pinfunction "86_86") (pintype "passive+no_connect"))
    )
    (net (code "173") (name "unconnected-(JM2-Pad87)") (class "Default")
      (node (ref "JM2") (pin "87") (pinfunction "87_87") (pintype "passive+no_connect"))
    )
    (net (code "174") (name "unconnected-(JM2-Pad88)") (class "Default")
      (node (ref "JM2") (pin "88") (pinfunction "88_88") (pintype "passive+no_connect"))
    )
    (net (code "175") (name "unconnected-(JM2-Pad89)") (class "Default")
      (node (ref "JM2") (pin "89") (pinfunction "89_89") (pintype "passive+no_connect"))
    )
    (net (code "176") (name "unconnected-(JM2-Pad92)") (class "Default")
      (node (ref "JM2") (pin "92") (pinfunction "92_92") (pintype "passive+no_connect"))
    )
    (net (code "177") (name "unconnected-(JM2-Pad94)") (class "Default")
      (node (ref "JM2") (pin "94") (pinfunction "94_94") (pintype "passive+no_connect"))
    )
    (net (code "178") (name "unconnected-(JM2-Pad96)") (class "Default")
      (node (ref "JM2") (pin "96") (pinfunction "96_96") (pintype "passive+no_connect"))
    )
    (net (code "179") (name "unconnected-(JM2-Pad98)") (class "Default")
      (node (ref "JM2") (pin "98") (pinfunction "98_98") (pintype "passive+no_connect"))
    )
    (net (code "180") (name "unconnected-(JM2-Pad100)") (class "Default")
      (node (ref "JM2") (pin "100") (pinfunction "100_100") (pintype "passive+no_connect"))
    )
    (net (code "181") (name "unconnected-(JM3-Pad1)") (class "Default")
      (node (ref "JM3") (pin "1") (pinfunction "1_1") (pintype "passive+no_connect"))
    )
    (net (code "182") (name "unconnected-(JM3-Pad2)") (class "Default")
      (node (ref "JM3") (pin "2") (pinfunction "2_2") (pintype "passive+no_connect"))
    )
    (net (code "183") (name "unconnected-(JM3-Pad3)") (class "Default")
      (node (ref "JM3") (pin "3") (pinfunction "3_3") (pintype "passive+no_connect"))
    )
    (net (code "184") (name "unconnected-(JM3-Pad4)") (class "Default")
      (node (ref "JM3") (pin "4") (pinfunction "4_4") (pintype "passive+no_connect"))
    )
    (net (code "185") (name "unconnected-(JM3-Pad32)") (class "Default")
      (node (ref "JM3") (pin "32") (pinfunction "32_32") (pintype "passive+no_connect"))
    )
    (net (code "186") (name "unconnected-(JM3-Pad34)") (class "Default")
      (node (ref "JM3") (pin "34") (pinfunction "34_34") (pintype "passive+no_connect"))
    )
    (net (code "187") (name "unconnected-(JM3-Pad37)") (class "Default")
      (node (ref "JM3") (pin "37") (pinfunction "37_37") (pintype "passive+no_connect"))
    )
    (net (code "188") (name "unconnected-(JM3-Pad38)") (class "Default")
      (node (ref "JM3") (pin "38") (pinfunction "38_38") (pintype "passive+no_connect"))
    )
    (net (code "189") (name "unconnected-(JM3-Pad39)") (class "Default")
      (node (ref "JM3") (pin "39") (pinfunction "39_39") (pintype "passive+no_connect"))
    )
    (net (code "190") (name "unconnected-(JM3-Pad40)") (class "Default")
      (node (ref "JM3") (pin "40") (pinfunction "40_40") (pintype "passive+no_connect"))
    )
    (net (code "191") (name "unconnected-(JM3-Pad41)") (class "Default")
      (node (ref "JM3") (pin "41") (pinfunction "41_41") (pintype "passive+no_connect"))
    )
    (net (code "192") (name "unconnected-(JM3-Pad42)") (class "Default")
      (node (ref "JM3") (pin "42") (pinfunction "42_42") (pintype "passive+no_connect"))
    )
    (net (code "193") (name "unconnected-(JM3-Pad43)") (class "Default")
      (node (ref "JM3") (pin "43") (pinfunction "43_43") (pintype "passive+no_connect"))
    )
    (net (code "194") (name "unconnected-(JM3-Pad44)") (class "Default")
      (node (ref "JM3") (pin "44") (pinfunction "44_44") (pintype "passive+no_connect"))
    )
    (net (code "195") (name "unconnected-(JM3-Pad47)") (class "Default")
      (node (ref "JM3") (pin "47") (pinfunction "47_47") (pintype "passive+no_connect"))
    )
    (net (code "196") (name "unconnected-(JM3-Pad48)") (class "Default")
      (node (ref "JM3") (pin "48") (pinfunction "48_48") (pintype "passive+no_connect"))
    )
    (net (code "197") (name "unconnected-(JM3-Pad49)") (class "Default")
      (node (ref "JM3") (pin "49") (pinfunction "49_49") (pintype "passive+no_connect"))
    )
    (net (code "198") (name "unconnected-(JM3-Pad50)") (class "Default")
      (node (ref "JM3") (pin "50") (pinfunction "50_50") (pintype "passive+no_connect"))
    )
    (net (code "199") (name "unconnected-(JM3-Pad51)") (class "Default")
      (node (ref "JM3") (pin "51") (pinfunction "51_51") (pintype "passive+no_connect"))
    )
    (net (code "200") (name "unconnected-(JM3-Pad52)") (class "Default")
      (node (ref "JM3") (pin "52") (pinfunction "52_52") (pintype "passive+no_connect"))
    )
    (net (code "201") (name "unconnected-(JM3-Pad53)") (class "Default")
      (node (ref "JM3") (pin "53") (pinfunction "53_53") (pintype "passive+no_connect"))
    )
    (net (code "202") (name "unconnected-(JM3-Pad54)") (class "Default")
      (node (ref "JM3") (pin "54") (pinfunction "54_54") (pintype "passive+no_connect"))
    )
    (net (code "203") (name "unconnected-(JM3-Pad55)") (class "Default")
      (node (ref "JM3") (pin "55") (pinfunction "55_55") (pintype "passive+no_connect"))
    )
    (net (code "204") (name "unconnected-(JM3-Pad56)") (class "Default")
      (node (ref "JM3") (pin "56") (pinfunction "56_56") (pintype "passive+no_connect"))
    )
    (net (code "205") (name "unconnected-(JM3-Pad57)") (class "Default")
      (node (ref "JM3") (pin "57") (pinfunction "57_57") (pintype "passive+no_connect"))
    )
    (net (code "206") (name "unconnected-(JM3-Pad58)") (class "Default")
      (node (ref "JM3") (pin "58") (pinfunction "58_58") (pintype "passive+no_connect"))
    )
    (net (code "207") (name "unconnected-(JM3-Pad60)") (class "Default")
      (node (ref "JM3") (pin "60") (pinfunction "60_60") (pintype "passive+no_connect"))
    )
  )
)
